# HandschuhGyro.net
KiCad netlist of a schematic drawn in EAGLE
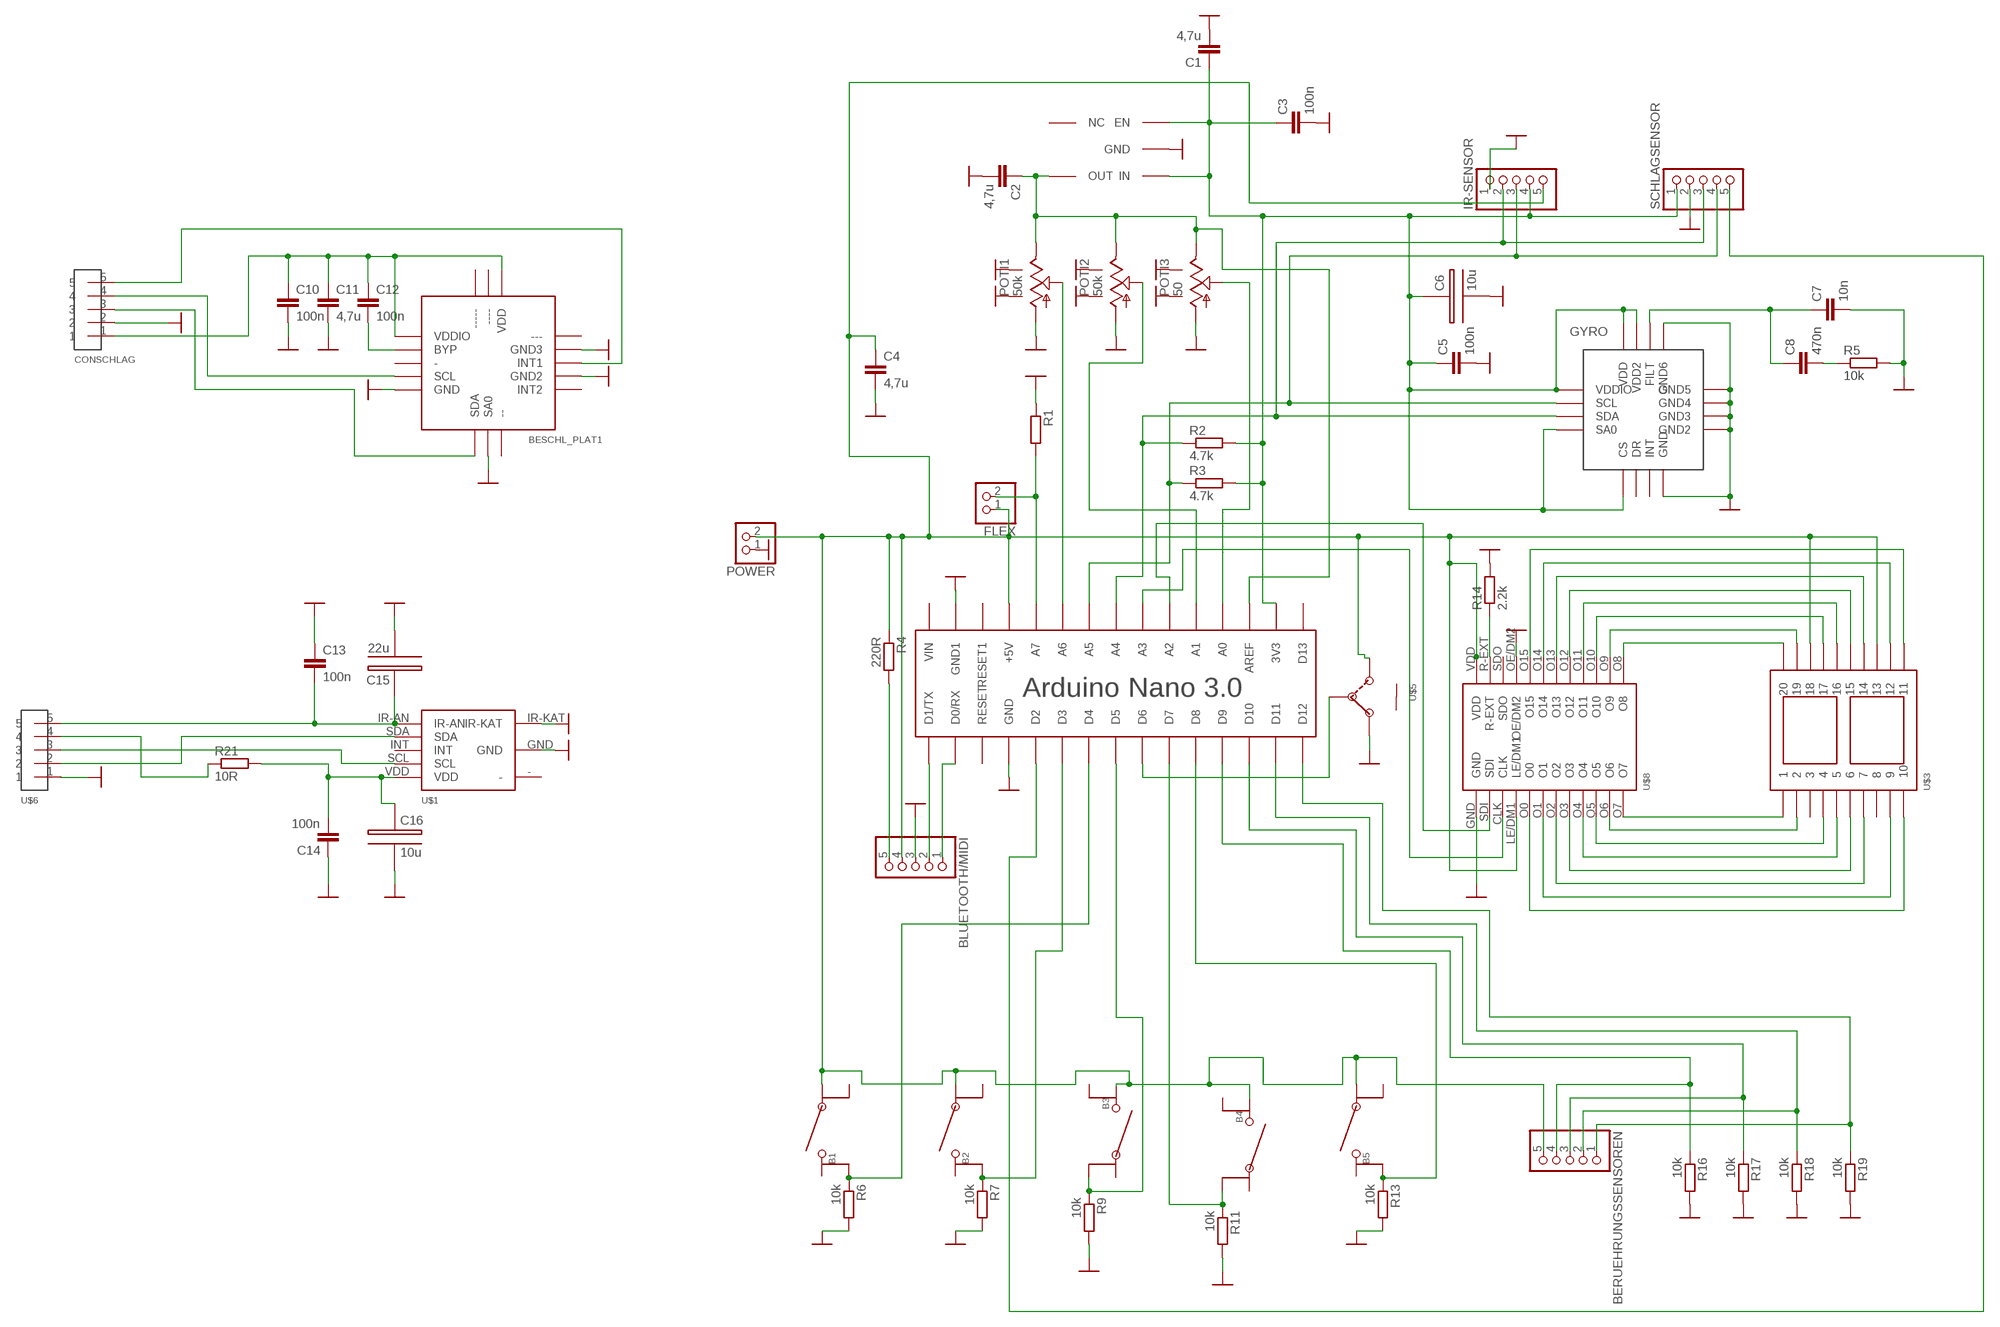
[diagram p0: schematic, sheet 1]

(export (version "E")
  (design (tool "Eeschema 10.0.6"))
  (components
    (comp (ref "B1")
      (value "BUTTON")
      (footprint "eagle-import:BUTTON")
      (libsource (lib "eagle-import") (part "BUTTON"))
    )
    (comp (ref "B2")
      (value "BUTTON")
      (footprint "eagle-import:BUTTON")
      (libsource (lib "eagle-import") (part "BUTTON"))
    )
    (comp (ref "B3")
      (value "BUTTON")
      (footprint "eagle-import:BUTTON")
      (libsource (lib "eagle-import") (part "BUTTON"))
    )
    (comp (ref "B4")
      (value "BUTTON")
      (footprint "eagle-import:BUTTON")
      (libsource (lib "eagle-import") (part "BUTTON"))
    )
    (comp (ref "B5")
      (value "BUTTON")
      (footprint "eagle-import:BUTTON")
      (libsource (lib "eagle-import") (part "BUTTON"))
    )
    (comp (ref "BERUEHRUNGSSENSOREN")
      (value "PINHD-1X5")
      (footprint "eagle-import:1X05")
      (libsource (lib "eagle-import") (part "PINHD-1X5"))
    )
    (comp (ref "BESCHL_PLAT1")
      (value "BESCHLEUNIGSUNGSSENSOR")
      (footprint "eagle-import:BESCHLEUNIGUNGSSENSOR")
      (libsource (lib "eagle-import") (part "BESCHLEUNIGSUNGSSENSOR"))
    )
    (comp (ref "BLUETOOTH/MIDI")
      (value "PINHD-1X5")
      (footprint "eagle-import:1X05")
      (libsource (lib "eagle-import") (part "PINHD-1X5"))
    )
    (comp (ref "C1")
      (value "4,7u")
      (footprint "eagle-import:C0805")
      (libsource (lib "eagle-import") (part "C-EUC0805"))
    )
    (comp (ref "C2")
      (value "4,7u")
      (footprint "eagle-import:C0805")
      (libsource (lib "eagle-import") (part "C-EUC0805"))
    )
    (comp (ref "C3")
      (value "100n")
      (footprint "eagle-import:C0805")
      (libsource (lib "eagle-import") (part "C-EUC0805"))
    )
    (comp (ref "C4")
      (value "4,7u")
      (footprint "eagle-import:C0805")
      (libsource (lib "eagle-import") (part "C-EUC0805"))
    )
    (comp (ref "C5")
      (value "100n")
      (footprint "eagle-import:C0805")
      (libsource (lib "eagle-import") (part "C-EUC0805"))
    )
    (comp (ref "C6")
      (value "10u")
      (footprint "eagle-import:22U-KONDENSATOR")
      (libsource (lib "eagle-import") (part "22U-KONDENSATOR"))
    )
    (comp (ref "C7")
      (value "10n")
      (footprint "eagle-import:C0805")
      (libsource (lib "eagle-import") (part "C-EUC0805"))
    )
    (comp (ref "C8")
      (value "470n")
      (footprint "eagle-import:C0805")
      (libsource (lib "eagle-import") (part "C-EUC0805"))
    )
    (comp (ref "C10")
      (value "100n")
      (footprint "eagle-import:C0805")
      (libsource (lib "eagle-import") (part "C-EUC0805"))
    )
    (comp (ref "C11")
      (value "4,7u")
      (footprint "eagle-import:C0805")
      (libsource (lib "eagle-import") (part "C-EUC0805"))
    )
    (comp (ref "C12")
      (value "100n")
      (footprint "eagle-import:C0805")
      (libsource (lib "eagle-import") (part "C-EUC0805"))
    )
    (comp (ref "C13")
      (value "100n")
      (footprint "eagle-import:C0805")
      (libsource (lib "eagle-import") (part "C-EUC0805"))
    )
    (comp (ref "C14")
      (value "100n")
      (footprint "eagle-import:C0805")
      (libsource (lib "eagle-import") (part "C-EUC0805"))
    )
    (comp (ref "C15")
      (value "22u")
      (footprint "eagle-import:22U-KONDENSATOR")
      (libsource (lib "eagle-import") (part "22U-KONDENSATOR"))
    )
    (comp (ref "C16")
      (value "10u")
      (footprint "eagle-import:22U-KONDENSATOR")
      (libsource (lib "eagle-import") (part "22U-KONDENSATOR"))
    )
    (comp (ref "CONSCHLAG")
      (value "BREAKBOARDCON2")
      (footprint "eagle-import:BREAKBOARDCON")
      (libsource (lib "eagle-import") (part "BREAKBOARDCON2"))
    )
    (comp (ref "FLEX")
      (value "PINHD-1X2")
      (footprint "eagle-import:1X02")
      (libsource (lib "eagle-import") (part "PINHD-1X2"))
    )
    (comp (ref "GYRO")
      (value "GYRO")
      (footprint "eagle-import:GYRO")
      (libsource (lib "eagle-import") (part "GYRO"))
    )
    (comp (ref "IR-SENSOR")
      (value "PINHD-1X5")
      (footprint "eagle-import:1X05")
      (libsource (lib "eagle-import") (part "PINHD-1X5"))
    )
    (comp (ref "POTI1")
      (value "50k")
      (footprint "eagle-import:POTI")
      (libsource (lib "eagle-import") (part "POTI"))
    )
    (comp (ref "POTI2")
      (value "50k")
      (footprint "eagle-import:POTI")
      (libsource (lib "eagle-import") (part "POTI"))
    )
    (comp (ref "POTI3")
      (value "50")
      (footprint "eagle-import:POTI")
      (libsource (lib "eagle-import") (part "POTI"))
    )
    (comp (ref "POWER")
      (value "PINHD-1X2")
      (footprint "eagle-import:1X02")
      (libsource (lib "eagle-import") (part "PINHD-1X2"))
    )
    (comp (ref "R1")
      (value "R-EU_M0805")
      (footprint "eagle-import:M0805")
      (libsource (lib "eagle-import") (part "R-EU_M0805"))
    )
    (comp (ref "R2")
      (value "4.7k")
      (footprint "eagle-import:M0805")
      (libsource (lib "eagle-import") (part "R-EU_M0805"))
    )
    (comp (ref "R3")
      (value "4.7k")
      (footprint "eagle-import:M0805")
      (libsource (lib "eagle-import") (part "R-EU_M0805"))
    )
    (comp (ref "R4")
      (value "220R")
      (footprint "eagle-import:M0805")
      (libsource (lib "eagle-import") (part "R-EU_M0805"))
    )
    (comp (ref "R5")
      (value "10k")
      (footprint "eagle-import:M0805")
      (libsource (lib "eagle-import") (part "R-EU_M0805"))
    )
    (comp (ref "R6")
      (value "10k")
      (footprint "eagle-import:M0805")
      (libsource (lib "eagle-import") (part "R-EU_M0805"))
    )
    (comp (ref "R7")
      (value "10k")
      (footprint "eagle-import:M0805")
      (libsource (lib "eagle-import") (part "R-EU_M0805"))
    )
    (comp (ref "R9")
      (value "10k")
      (footprint "eagle-import:M0805")
      (libsource (lib "eagle-import") (part "R-EU_M0805"))
    )
    (comp (ref "R11")
      (value "10k")
      (footprint "eagle-import:M0805")
      (libsource (lib "eagle-import") (part "R-EU_M0805"))
    )
    (comp (ref "R13")
      (value "10k")
      (footprint "eagle-import:M0805")
      (libsource (lib "eagle-import") (part "R-EU_M0805"))
    )
    (comp (ref "R14")
      (value "2.2k")
      (footprint "eagle-import:M0805")
      (libsource (lib "eagle-import") (part "R-EU_M0805"))
    )
    (comp (ref "R16")
      (value "10k")
      (footprint "eagle-import:M0805")
      (libsource (lib "eagle-import") (part "R-EU_M0805"))
    )
    (comp (ref "R17")
      (value "10k")
      (footprint "eagle-import:M0805")
      (libsource (lib "eagle-import") (part "R-EU_M0805"))
    )
    (comp (ref "R18")
      (value "10k")
      (footprint "eagle-import:M0805")
      (libsource (lib "eagle-import") (part "R-EU_M0805"))
    )
    (comp (ref "R19")
      (value "10k")
      (footprint "eagle-import:M0805")
      (libsource (lib "eagle-import") (part "R-EU_M0805"))
    )
    (comp (ref "R21")
      (value "10R")
      (footprint "eagle-import:M0805")
      (libsource (lib "eagle-import") (part "R-EU_M0805"))
    )
    (comp (ref "SCHLAGSENSOR")
      (value "PINHD-1X5")
      (footprint "eagle-import:1X05")
      (libsource (lib "eagle-import") (part "PINHD-1X5"))
    )
    (comp (ref "U$1")
      (value "IR-SENSOR")
      (footprint "eagle-import:IR-SENSOR")
      (libsource (lib "eagle-import") (part "IR-SENSOR"))
    )
    (comp (ref "U$2")
      (value "ARDUINONANO")
      (footprint "eagle-import:PDIP-32")
      (libsource (lib "eagle-import") (part "ARDUINONANO"))
    )
    (comp (ref "U$3")
      (value "7-SEGMENT")
      (footprint "eagle-import:7-SEGMENT")
      (libsource (lib "eagle-import") (part "7-SEGMENT"))
    )
    (comp (ref "U$4")
      (value "1,1V-SPANNUNGSREGLER")
      (footprint "eagle-import:1,1V-SPANNUNGSREGLER")
      (libsource (lib "eagle-import") (part "1,1V-SPANNUNGSREGLER"))
    )
    (comp (ref "U$5")
      (value "SCHALTER")
      (footprint "eagle-import:SCHALTER")
      (libsource (lib "eagle-import") (part "SCHALTER"))
    )
    (comp (ref "U$6")
      (value "BREAKBOARDCON2")
      (footprint "eagle-import:BREAKBOARDCON")
      (libsource (lib "eagle-import") (part "BREAKBOARDCON2"))
    )
    (comp (ref "U$8")
      (value "7-SEGMENT-TREIBER")
      (footprint "eagle-import:7-SEGMENT-TREIBER")
      (libsource (lib "eagle-import") (part "7-SEGMENT-TREIBER"))
    )
  )
  (nets
    (net (code "1") (name "Net-(B1-Pad2)") (class "Default")
      (node (ref "B1") (pin "2") (pinfunction "2_2") (pintype "bidirectional"))
      (node (ref "R6") (pin "1") (pinfunction "1_1") (pintype "passive"))
      (node (ref "U$2") (pin "D4") (pinfunction "D4_D4") (pintype "bidirectional"))
    )
    (net (code "2") (name "Net-(B1-Pad3)") (class "Default")
      (node (ref "B1") (pin "3") (pinfunction "3_3") (pintype "bidirectional"))
      (node (ref "B2") (pin "3") (pinfunction "3_3") (pintype "bidirectional"))
      (node (ref "B3") (pin "1") (pinfunction "1_1") (pintype "bidirectional"))
      (node (ref "B4") (pin "1") (pinfunction "1_1") (pintype "bidirectional"))
      (node (ref "B5") (pin "3") (pinfunction "3_3") (pintype "bidirectional"))
      (node (ref "BERUEHRUNGSSENSOREN") (pin "5") (pinfunction "5_5") (pintype "passive"))
      (node (ref "BLUETOOTH/MIDI") (pin "4") (pinfunction "4_4") (pintype "passive"))
      (node (ref "C4") (pin "1") (pinfunction "1_1") (pintype "passive"))
      (node (ref "FLEX") (pin "1") (pinfunction "1_1") (pintype "passive"))
      (node (ref "IR-SENSOR") (pin "5") (pinfunction "5_5") (pintype "passive"))
      (node (ref "POWER") (pin "2") (pinfunction "2_2") (pintype "passive"))
      (node (ref "R4") (pin "1") (pinfunction "1_1") (pintype "passive"))
      (node (ref "U$2") (pin "+5V") (pinfunction "+5V_+5V") (pintype "bidirectional"))
      (node (ref "U$3") (pin "13") (pinfunction "13_13") (pintype "bidirectional"))
      (node (ref "U$3") (pin "18") (pinfunction "18_18") (pintype "bidirectional"))
      (node (ref "U$5") (pin "3") (pinfunction "3_3") (pintype "bidirectional"))
      (node (ref "U$8") (pin "LE/DM1") (pinfunction "LE/DM1_LE/DM1") (pintype "bidirectional"))
      (node (ref "U$8") (pin "VDD") (pinfunction "VDD_VDD") (pintype "bidirectional"))
    )
    (net (code "3") (name "Net-(B2-Pad2)") (class "Default")
      (node (ref "B2") (pin "2") (pinfunction "2_2") (pintype "bidirectional"))
      (node (ref "R7") (pin "1") (pinfunction "1_1") (pintype "passive"))
      (node (ref "U$2") (pin "D3") (pinfunction "D3_D3") (pintype "bidirectional"))
    )
    (net (code "4") (name "Net-(B3-Pad4)") (class "Default")
      (node (ref "B3") (pin "4") (pinfunction "4_4") (pintype "bidirectional"))
      (node (ref "R9") (pin "1") (pinfunction "1_1") (pintype "passive"))
      (node (ref "U$2") (pin "D5") (pinfunction "D5_D5") (pintype "bidirectional"))
    )
    (net (code "5") (name "Net-(B4-Pad4)") (class "Default")
      (node (ref "B4") (pin "4") (pinfunction "4_4") (pintype "bidirectional"))
      (node (ref "R11") (pin "1") (pinfunction "1_1") (pintype "passive"))
      (node (ref "U$2") (pin "D7") (pinfunction "D7_D7") (pintype "bidirectional"))
    )
    (net (code "6") (name "Net-(B5-Pad2)") (class "Default")
      (node (ref "B5") (pin "2") (pinfunction "2_2") (pintype "bidirectional"))
      (node (ref "R13") (pin "1") (pinfunction "1_1") (pintype "passive"))
      (node (ref "U$2") (pin "D8") (pinfunction "D8_D8") (pintype "bidirectional"))
    )
    (net (code "7") (name "Net-(BERUEHRUNGSSENSOREN-Pad1)") (class "Default")
      (node (ref "BERUEHRUNGSSENSOREN") (pin "1") (pinfunction "1_1") (pintype "passive"))
      (node (ref "R19") (pin "1") (pinfunction "1_1") (pintype "passive"))
      (node (ref "U$2") (pin "D12") (pinfunction "D12_D12") (pintype "bidirectional"))
    )
    (net (code "8") (name "Net-(BERUEHRUNGSSENSOREN-Pad2)") (class "Default")
      (node (ref "BERUEHRUNGSSENSOREN") (pin "2") (pinfunction "2_2") (pintype "passive"))
      (node (ref "R18") (pin "1") (pinfunction "1_1") (pintype "passive"))
      (node (ref "U$2") (pin "D11") (pinfunction "D11_D11") (pintype "bidirectional"))
    )
    (net (code "9") (name "Net-(BERUEHRUNGSSENSOREN-Pad3)") (class "Default")
      (node (ref "BERUEHRUNGSSENSOREN") (pin "3") (pinfunction "3_3") (pintype "passive"))
      (node (ref "R17") (pin "1") (pinfunction "1_1") (pintype "passive"))
      (node (ref "U$2") (pin "D10") (pinfunction "D10_D10") (pintype "bidirectional"))
    )
    (net (code "10") (name "Net-(BERUEHRUNGSSENSOREN-Pad4)") (class "Default")
      (node (ref "BERUEHRUNGSSENSOREN") (pin "4") (pinfunction "4_4") (pintype "passive"))
      (node (ref "R16") (pin "1") (pinfunction "1_1") (pintype "passive"))
      (node (ref "U$2") (pin "D9") (pinfunction "D9_D9") (pintype "bidirectional"))
    )
    (net (code "11") (name "Net-(BESCHL_PLAT1-PadBYP)") (class "Default")
      (node (ref "BESCHL_PLAT1") (pin "BYP") (pinfunction "BYP_BYP") (pintype "bidirectional"))
      (node (ref "C12") (pin "2") (pinfunction "2_2") (pintype "passive"))
    )
    (net (code "12") (name "Net-(BESCHL_PLAT1-PadINT1)") (class "Default")
      (node (ref "BESCHL_PLAT1") (pin "INT1") (pinfunction "INT1_INT1") (pintype "bidirectional"))
      (node (ref "CONSCHLAG") (pin "5") (pinfunction "5_5") (pintype "bidirectional"))
    )
    (net (code "13") (name "Net-(BESCHL_PLAT1-PadSCL)") (class "Default")
      (node (ref "BESCHL_PLAT1") (pin "SCL") (pinfunction "SCL_SCL") (pintype "bidirectional"))
      (node (ref "CONSCHLAG") (pin "4") (pinfunction "4_4") (pintype "bidirectional"))
    )
    (net (code "14") (name "Net-(BESCHL_PLAT1-PadSDA)") (class "Default")
      (node (ref "BESCHL_PLAT1") (pin "SDA") (pinfunction "SDA_SDA") (pintype "bidirectional"))
      (node (ref "CONSCHLAG") (pin "3") (pinfunction "3_3") (pintype "bidirectional"))
    )
    (net (code "15") (name "Net-(BESCHL_PLAT1-PadVDD)") (class "Default")
      (node (ref "BESCHL_PLAT1") (pin "VDD") (pinfunction "VDD_VDD") (pintype "bidirectional"))
      (node (ref "BESCHL_PLAT1") (pin "VDDIO") (pinfunction "VDDIO_VDDIO") (pintype "bidirectional"))
      (node (ref "C10") (pin "1") (pinfunction "1_1") (pintype "passive"))
      (node (ref "C11") (pin "1") (pinfunction "1_1") (pintype "passive"))
      (node (ref "C12") (pin "1") (pinfunction "1_1") (pintype "passive"))
      (node (ref "CONSCHLAG") (pin "1") (pinfunction "1_1") (pintype "bidirectional"))
    )
    (net (code "16") (name "Net-(BLUETOOTH/MIDI-Pad1)") (class "Default")
      (node (ref "BLUETOOTH/MIDI") (pin "1") (pinfunction "1_1") (pintype "passive"))
      (node (ref "U$2") (pin "D0/RX") (pinfunction "D0/RX_D0/RX") (pintype "bidirectional"))
    )
    (net (code "17") (name "Net-(BLUETOOTH/MIDI-Pad2)") (class "Default")
      (node (ref "BLUETOOTH/MIDI") (pin "2") (pinfunction "2_2") (pintype "passive"))
      (node (ref "U$2") (pin "D1/TX") (pinfunction "D1/TX_D1/TX") (pintype "bidirectional"))
    )
    (net (code "18") (name "Net-(BLUETOOTH/MIDI-Pad5)") (class "Default")
      (node (ref "BLUETOOTH/MIDI") (pin "5") (pinfunction "5_5") (pintype "passive"))
      (node (ref "R4") (pin "2") (pinfunction "2_2") (pintype "passive"))
    )
    (net (code "19") (name "Net-(C1-Pad1)") (class "Default")
      (node (ref "C1") (pin "1") (pinfunction "1_1") (pintype "passive"))
      (node (ref "C3") (pin "1") (pinfunction "1_1") (pintype "passive"))
      (node (ref "C5") (pin "1") (pinfunction "1_1") (pintype "passive"))
      (node (ref "C6") (pin "+") (pinfunction "+_+") (pintype "bidirectional"))
      (node (ref "GYRO") (pin "CS") (pinfunction "CS_CS") (pintype "bidirectional"))
      (node (ref "GYRO") (pin "SA0") (pinfunction "SA0_SA0") (pintype "bidirectional"))
      (node (ref "GYRO") (pin "VDD") (pinfunction "VDD_VDD") (pintype "bidirectional"))
      (node (ref "GYRO") (pin "VDD2") (pinfunction "VDD2_VDD2") (pintype "bidirectional"))
      (node (ref "GYRO") (pin "VDDIO") (pinfunction "VDDIO_VDDIO") (pintype "bidirectional"))
      (node (ref "IR-SENSOR") (pin "4") (pinfunction "4_4") (pintype "passive"))
      (node (ref "R2") (pin "2") (pinfunction "2_2") (pintype "passive"))
      (node (ref "R3") (pin "2") (pinfunction "2_2") (pintype "passive"))
      (node (ref "SCHLAGSENSOR") (pin "1") (pinfunction "1_1") (pintype "passive"))
      (node (ref "U$2") (pin "3V3") (pinfunction "3V3_3V3") (pintype "bidirectional"))
      (node (ref "U$4") (pin "EN") (pinfunction "EN_EN") (pintype "bidirectional"))
      (node (ref "U$4") (pin "IN") (pinfunction "IN_IN") (pintype "bidirectional"))
    )
    (net (code "20") (name "Net-(C2-Pad1)") (class "Default")
      (node (ref "C2") (pin "1") (pinfunction "1_1") (pintype "passive"))
      (node (ref "POTI1") (pin "VCC") (pinfunction "VCC_VCC") (pintype "passive"))
      (node (ref "POTI2") (pin "VCC") (pinfunction "VCC_VCC") (pintype "passive"))
      (node (ref "POTI3") (pin "VCC") (pinfunction "VCC_VCC") (pintype "passive"))
      (node (ref "U$2") (pin "AREF") (pinfunction "AREF_AREF") (pintype "bidirectional"))
      (node (ref "U$4") (pin "OUT") (pinfunction "OUT_OUT") (pintype "bidirectional"))
    )
    (net (code "21") (name "Net-(C7-Pad1)") (class "Default")
      (node (ref "C7") (pin "1") (pinfunction "1_1") (pintype "passive"))
      (node (ref "C8") (pin "1") (pinfunction "1_1") (pintype "passive"))
      (node (ref "GYRO") (pin "FILT") (pinfunction "FILT_FILT") (pintype "bidirectional"))
    )
    (net (code "22") (name "Net-(C8-Pad2)") (class "Default")
      (node (ref "C8") (pin "2") (pinfunction "2_2") (pintype "passive"))
      (node (ref "R5") (pin "1") (pinfunction "1_1") (pintype "passive"))
    )
    (net (code "23") (name "Net-(C13-Pad2)") (class "Default")
      (node (ref "C13") (pin "2") (pinfunction "2_2") (pintype "passive"))
      (node (ref "C15") (pin "+") (pinfunction "+_+") (pintype "bidirectional"))
      (node (ref "U$1") (pin "IR-AN") (pinfunction "IR-AN_IR-AN") (pintype "bidirectional"))
      (node (ref "U$6") (pin "5") (pinfunction "5_5") (pintype "bidirectional"))
    )
    (net (code "24") (name "Net-(C14-Pad2)") (class "Default")
      (node (ref "C14") (pin "2") (pinfunction "2_2") (pintype "passive"))
      (node (ref "C16") (pin "+") (pinfunction "+_+") (pintype "bidirectional"))
      (node (ref "R21") (pin "2") (pinfunction "2_2") (pintype "passive"))
      (node (ref "U$1") (pin "VDD") (pinfunction "VDD_VDD") (pintype "bidirectional"))
    )
    (net (code "25") (name "Net-(R14-Pad1)") (class "Default")
      (node (ref "R14") (pin "1") (pinfunction "1_1") (pintype "passive"))
      (node (ref "U$8") (pin "R-EXT") (pinfunction "R-EXT_R-EXT") (pintype "bidirectional"))
    )
    (net (code "26") (name "Net-(R21-Pad1)") (class "Default")
      (node (ref "R21") (pin "1") (pinfunction "1_1") (pintype "passive"))
      (node (ref "U$6") (pin "4") (pinfunction "4_4") (pintype "bidirectional"))
    )
    (net (code "27") (name "Net-(SCHLAGSENSOR-Pad5)") (class "Default")
      (node (ref "SCHLAGSENSOR") (pin "5") (pinfunction "5_5") (pintype "passive"))
      (node (ref "U$2") (pin "D2") (pinfunction "D2_D2") (pintype "bidirectional"))
    )
    (net (code "28") (name "Net-(U$1-PadSCL)") (class "Default")
      (node (ref "U$1") (pin "SCL") (pinfunction "SCL_SCL") (pintype "bidirectional"))
      (node (ref "U$6") (pin "3") (pinfunction "3_3") (pintype "bidirectional"))
    )
    (net (code "29") (name "Net-(U$1-PadSDA)") (class "Default")
      (node (ref "U$1") (pin "SDA") (pinfunction "SDA_SDA") (pintype "bidirectional"))
      (node (ref "U$6") (pin "2") (pinfunction "2_2") (pintype "bidirectional"))
    )
    (net (code "30") (name "Net-(U$2-A0)") (class "Default")
      (node (ref "POTI3") (pin "VALUE") (pinfunction "VALUE_VALUE") (pintype "passive"))
      (node (ref "U$2") (pin "A7") (pinfunction "A0_A7") (pintype "bidirectional"))
    )
    (net (code "31") (name "Net-(U$2-A1)") (class "Default")
      (node (ref "POTI2") (pin "VALUE") (pinfunction "VALUE_VALUE") (pintype "passive"))
      (node (ref "U$2") (pin "A6") (pinfunction "A1_A6") (pintype "bidirectional"))
    )
    (net (code "32") (name "Net-(U$2-A2)") (class "Default")
      (node (ref "U$2") (pin "A5") (pinfunction "A2_A5") (pintype "bidirectional"))
      (node (ref "U$8") (pin "SDI") (pinfunction "SDI_SDI") (pintype "bidirectional"))
    )
    (net (code "33") (name "Net-(U$2-A3)") (class "Default")
      (node (ref "U$2") (pin "A4") (pinfunction "A3_A4") (pintype "bidirectional"))
      (node (ref "U$8") (pin "CLK") (pinfunction "CLK_CLK") (pintype "bidirectional"))
    )
    (net (code "34") (name "Net-(U$2-A4)") (class "Default")
      (node (ref "GYRO") (pin "SDA") (pinfunction "SDA_SDA") (pintype "bidirectional"))
      (node (ref "IR-SENSOR") (pin "2") (pinfunction "2_2") (pintype "passive"))
      (node (ref "R2") (pin "1") (pinfunction "1_1") (pintype "passive"))
      (node (ref "SCHLAGSENSOR") (pin "3") (pinfunction "3_3") (pintype "passive"))
      (node (ref "U$2") (pin "A3") (pinfunction "A4_A3") (pintype "bidirectional"))
    )
    (net (code "35") (name "Net-(U$2-A5)") (class "Default")
      (node (ref "GYRO") (pin "SCL") (pinfunction "SCL_SCL") (pintype "bidirectional"))
      (node (ref "IR-SENSOR") (pin "3") (pinfunction "3_3") (pintype "passive"))
      (node (ref "R3") (pin "1") (pinfunction "1_1") (pintype "passive"))
      (node (ref "SCHLAGSENSOR") (pin "4") (pinfunction "4_4") (pintype "passive"))
      (node (ref "U$2") (pin "A2") (pinfunction "A5_A2") (pintype "bidirectional"))
    )
    (net (code "36") (name "Net-(U$2-A6)") (class "Default")
      (node (ref "POTI1") (pin "VALUE") (pinfunction "VALUE_VALUE") (pintype "passive"))
      (node (ref "U$2") (pin "A1") (pinfunction "A6_A1") (pintype "bidirectional"))
    )
    (net (code "37") (name "Net-(U$2-A7)") (class "Default")
      (node (ref "FLEX") (pin "2") (pinfunction "2_2") (pintype "passive"))
      (node (ref "R1") (pin "2") (pinfunction "2_2") (pintype "passive"))
      (node (ref "U$2") (pin "A0") (pinfunction "A7_A0") (pintype "bidirectional"))
    )
    (net (code "38") (name "Net-(U$2-PadD6)") (class "Default")
      (node (ref "U$2") (pin "D6") (pinfunction "D6_D6") (pintype "bidirectional"))
      (node (ref "U$5") (pin "2") (pinfunction "2_2") (pintype "bidirectional"))
    )
    (net (code "39") (name "Net-(U$3-Pad1)") (class "Default")
      (node (ref "U$3") (pin "1") (pinfunction "1_1") (pintype "bidirectional"))
      (node (ref "U$8") (pin "O7") (pinfunction "O7_O7") (pintype "bidirectional"))
    )
    (net (code "40") (name "Net-(U$3-Pad2)") (class "Default")
      (node (ref "U$3") (pin "2") (pinfunction "2_2") (pintype "bidirectional"))
      (node (ref "U$8") (pin "O6") (pinfunction "O6_O6") (pintype "bidirectional"))
    )
    (net (code "41") (name "Net-(U$3-Pad4)") (class "Default")
      (node (ref "U$3") (pin "4") (pinfunction "4_4") (pintype "bidirectional"))
      (node (ref "U$8") (pin "O5") (pinfunction "O5_O5") (pintype "bidirectional"))
    )
    (net (code "42") (name "Net-(U$3-Pad5)") (class "Default")
      (node (ref "U$3") (pin "5") (pinfunction "5_5") (pintype "bidirectional"))
      (node (ref "U$8") (pin "O4") (pinfunction "O4_O4") (pintype "bidirectional"))
    )
    (net (code "43") (name "Net-(U$3-Pad6)") (class "Default")
      (node (ref "U$3") (pin "6") (pinfunction "6_6") (pintype "bidirectional"))
      (node (ref "U$8") (pin "O3") (pinfunction "O3_O3") (pintype "bidirectional"))
    )
    (net (code "44") (name "Net-(U$3-Pad7)") (class "Default")
      (node (ref "U$3") (pin "7") (pinfunction "7_7") (pintype "bidirectional"))
      (node (ref "U$8") (pin "O2") (pinfunction "O2_O2") (pintype "bidirectional"))
    )
    (net (code "45") (name "Net-(U$3-Pad9)") (class "Default")
      (node (ref "U$3") (pin "9") (pinfunction "9_9") (pintype "bidirectional"))
      (node (ref "U$8") (pin "O1") (pinfunction "O1_O1") (pintype "bidirectional"))
    )
    (net (code "46") (name "Net-(U$3-Pad10)") (class "Default")
      (node (ref "U$3") (pin "10") (pinfunction "10_10") (pintype "bidirectional"))
      (node (ref "U$8") (pin "O0") (pinfunction "O0_O0") (pintype "bidirectional"))
    )
    (net (code "47") (name "Net-(U$3-Pad11)") (class "Default")
      (node (ref "U$3") (pin "11") (pinfunction "11_11") (pintype "bidirectional"))
      (node (ref "U$8") (pin "O15") (pinfunction "O15_O15") (pintype "bidirectional"))
    )
    (net (code "48") (name "Net-(U$3-Pad12)") (class "Default")
      (node (ref "U$3") (pin "12") (pinfunction "12_12") (pintype "bidirectional"))
      (node (ref "U$8") (pin "O14") (pinfunction "O14_O14") (pintype "bidirectional"))
    )
    (net (code "49") (name "Net-(U$3-Pad14)") (class "Default")
      (node (ref "U$3") (pin "14") (pinfunction "14_14") (pintype "bidirectional"))
      (node (ref "U$8") (pin "O13") (pinfunction "O13_O13") (pintype "bidirectional"))
    )
    (net (code "50") (name "Net-(U$3-Pad15)") (class "Default")
      (node (ref "U$3") (pin "15") (pinfunction "15_15") (pintype "bidirectional"))
      (node (ref "U$8") (pin "O12") (pinfunction "O12_O12") (pintype "bidirectional"))
    )
    (net (code "51") (name "Net-(U$3-Pad16)") (class "Default")
      (node (ref "U$3") (pin "16") (pinfunction "16_16") (pintype "bidirectional"))
      (node (ref "U$8") (pin "O11") (pinfunction "O11_O11") (pintype "bidirectional"))
    )
    (net (code "52") (name "Net-(U$3-Pad17)") (class "Default")
      (node (ref "U$3") (pin "17") (pinfunction "17_17") (pintype "bidirectional"))
      (node (ref "U$8") (pin "O10") (pinfunction "O10_O10") (pintype "bidirectional"))
    )
    (net (code "53") (name "Net-(U$3-Pad19)") (class "Default")
      (node (ref "U$3") (pin "19") (pinfunction "19_19") (pintype "bidirectional"))
      (node (ref "U$8") (pin "O9") (pinfunction "O9_O9") (pintype "bidirectional"))
    )
    (net (code "54") (name "Net-(U$3-Pad20)") (class "Default")
      (node (ref "U$3") (pin "20") (pinfunction "20_20") (pintype "bidirectional"))
      (node (ref "U$8") (pin "O8") (pinfunction "O8_O8") (pintype "bidirectional"))
    )
    (net (code "55") (name "POWER_SUPPLY1_GND") (class "Default")
      (node (ref "BESCHL_PLAT1") (pin "GND") (pinfunction "GND_GND") (pintype "bidirectional"))
      (node (ref "BESCHL_PLAT1") (pin "GND2") (pinfunction "GND2_GND2") (pintype "bidirectional"))
      (node (ref "BESCHL_PLAT1") (pin "GND3") (pinfunction "GND3_GND3") (pintype "bidirectional"))
      (node (ref "BESCHL_PLAT1") (pin "SA0") (pinfunction "SA0_SA0") (pintype "bidirectional"))
      (node (ref "BLUETOOTH/MIDI") (pin "3") (pinfunction "3_3") (pintype "passive"))
      (node (ref "C1") (pin "2") (pinfunction "2_2") (pintype "passive"))
      (node (ref "C10") (pin "2") (pinfunction "2_2") (pintype "passive"))
      (node (ref "C11") (pin "2") (pinfunction "2_2") (pintype "passive"))
      (node (ref "C13") (pin "1") (pinfunction "1_1") (pintype "passive"))
      (node (ref "C14") (pin "1") (pinfunction "1_1") (pintype "passive"))
      (node (ref "C15") (pin "-") (pinfunction "-_-") (pintype "bidirectional"))
      (node (ref "C16") (pin "-") (pinfunction "-_-") (pintype "bidirectional"))
      (node (ref "C2") (pin "2") (pinfunction "2_2") (pintype "passive"))
      (node (ref "C3") (pin "2") (pinfunction "2_2") (pintype "passive"))
      (node (ref "C4") (pin "2") (pinfunction "2_2") (pintype "passive"))
      (node (ref "C5") (pin "2") (pinfunction "2_2") (pintype "passive"))
      (node (ref "C6") (pin "-") (pinfunction "-_-") (pintype "bidirectional"))
      (node (ref "C7") (pin "2") (pinfunction "2_2") (pintype "passive"))
      (node (ref "CONSCHLAG") (pin "2") (pinfunction "2_2") (pintype "bidirectional"))
      (node (ref "GYRO") (pin "GND") (pinfunction "GND_GND") (pintype "bidirectional"))
      (node (ref "GYRO") (pin "GND2") (pinfunction "GND2_GND2") (pintype "bidirectional"))
      (node (ref "GYRO") (pin "GND3") (pinfunction "GND3_GND3") (pintype "bidirectional"))
      (node (ref "GYRO") (pin "GND4") (pinfunction "GND4_GND4") (pintype "bidirectional"))
      (node (ref "GYRO") (pin "GND5") (pinfunction "GND5_GND5") (pintype "bidirectional"))
      (node (ref "GYRO") (pin "GND6") (pinfunction "GND6_GND6") (pintype "bidirectional"))
      (node (ref "IR-SENSOR") (pin "1") (pinfunction "1_1") (pintype "passive"))
      (node (ref "POTI1") (pin "FIX1") (pinfunction "FUSS1_FIX1") (pintype "passive"))
      (node (ref "POTI1") (pin "FIX2") (pinfunction "FUSS2_FIX2") (pintype "passive"))
      (node (ref "POTI1") (pin "GND") (pinfunction "GND_GND") (pintype "passive"))
      (node (ref "POTI2") (pin "FIX1") (pinfunction "FUSS1_FIX1") (pintype "passive"))
      (node (ref "POTI2") (pin "FIX2") (pinfunction "FUSS2_FIX2") (pintype "passive"))
      (node (ref "POTI2") (pin "GND") (pinfunction "GND_GND") (pintype "passive"))
      (node (ref "POTI3") (pin "FIX1") (pinfunction "FUSS1_FIX1") (pintype "passive"))
      (node (ref "POTI3") (pin "FIX2") (pinfunction "FUSS2_FIX2") (pintype "passive"))
      (node (ref "POTI3") (pin "GND") (pinfunction "GND_GND") (pintype "passive"))
      (node (ref "POWER") (pin "1") (pinfunction "1_1") (pintype "passive"))
      (node (ref "R1") (pin "1") (pinfunction "1_1") (pintype "passive"))
      (node (ref "R11") (pin "2") (pinfunction "2_2") (pintype "passive"))
      (node (ref "R13") (pin "2") (pinfunction "2_2") (pintype "passive"))
      (node (ref "R14") (pin "2") (pinfunction "2_2") (pintype "passive"))
      (node (ref "R16") (pin "2") (pinfunction "2_2") (pintype "passive"))
      (node (ref "R17") (pin "2") (pinfunction "2_2") (pintype "passive"))
      (node (ref "R18") (pin "2") (pinfunction "2_2") (pintype "passive"))
      (node (ref "R19") (pin "2") (pinfunction "2_2") (pintype "passive"))
      (node (ref "R5") (pin "2") (pinfunction "2_2") (pintype "passive"))
      (node (ref "R6") (pin "2") (pinfunction "2_2") (pintype "passive"))
      (node (ref "R7") (pin "2") (pinfunction "2_2") (pintype "passive"))
      (node (ref "R9") (pin "2") (pinfunction "2_2") (pintype "passive"))
      (node (ref "SCHLAGSENSOR") (pin "2") (pinfunction "2_2") (pintype "passive"))
      (node (ref "U$1") (pin "GND") (pinfunction "GND_GND") (pintype "bidirectional"))
      (node (ref "U$1") (pin "IR-KAT") (pinfunction "IR-KAT_IR-KAT") (pintype "bidirectional"))
      (node (ref "U$2") (pin "GND") (pinfunction "GND_GND") (pintype "bidirectional"))
      (node (ref "U$2") (pin "GND1") (pinfunction "GND1_GND1") (pintype "bidirectional"))
      (node (ref "U$4") (pin "GND") (pinfunction "GND_GND") (pintype "bidirectional"))
      (node (ref "U$5") (pin "1") (pinfunction "1_1") (pintype "bidirectional"))
      (node (ref "U$6") (pin "1") (pinfunction "1_1") (pintype "bidirectional"))
      (node (ref "U$8") (pin "GND") (pinfunction "GND_GND") (pintype "bidirectional"))
      (node (ref "U$8") (pin "OE/DM2") (pinfunction "OE/DM2_OE/DM2") (pintype "bidirectional"))
    )
    (net (code "56") (name "unconnected-(B1-Pad1)") (class "Default")
      (node (ref "B1") (pin "1") (pinfunction "1_1") (pintype "bidirectional"))
    )
    (net (code "57") (name "unconnected-(B1-Pad4)") (class "Default")
      (node (ref "B1") (pin "4") (pinfunction "4_4") (pintype "bidirectional"))
    )
    (net (code "58") (name "unconnected-(B2-Pad1)") (class "Default")
      (node (ref "B2") (pin "1") (pinfunction "1_1") (pintype "bidirectional"))
    )
    (net (code "59") (name "unconnected-(B2-Pad4)") (class "Default")
      (node (ref "B2") (pin "4") (pinfunction "4_4") (pintype "bidirectional"))
    )
    (net (code "60") (name "unconnected-(B3-Pad2)") (class "Default")
      (node (ref "B3") (pin "2") (pinfunction "2_2") (pintype "bidirectional"))
    )
    (net (code "61") (name "unconnected-(B3-Pad3)") (class "Default")
      (node (ref "B3") (pin "3") (pinfunction "3_3") (pintype "bidirectional"))
    )
    (net (code "62") (name "unconnected-(B4-Pad2)") (class "Default")
      (node (ref "B4") (pin "2") (pinfunction "2_2") (pintype "bidirectional"))
    )
    (net (code "63") (name "unconnected-(B4-Pad3)") (class "Default")
      (node (ref "B4") (pin "3") (pinfunction "3_3") (pintype "bidirectional"))
    )
    (net (code "64") (name "unconnected-(B5-Pad1)") (class "Default")
      (node (ref "B5") (pin "1") (pinfunction "1_1") (pintype "bidirectional"))
    )
    (net (code "65") (name "unconnected-(B5-Pad4)") (class "Default")
      (node (ref "B5") (pin "4") (pinfunction "4_4") (pintype "bidirectional"))
    )
    (net (code "66") (name "unconnected-(BESCHL_PLAT1-Pad-)") (class "Default")
      (node (ref "BESCHL_PLAT1") (pin "-") (pinfunction "-_-") (pintype "bidirectional"))
    )
    (net (code "67") (name "unconnected-(BESCHL_PLAT1-Pad--)") (class "Default")
      (node (ref "BESCHL_PLAT1") (pin "--") (pinfunction "--_--") (pintype "bidirectional"))
    )
    (net (code "68") (name "unconnected-(BESCHL_PLAT1-Pad---)") (class "Default")
      (node (ref "BESCHL_PLAT1") (pin "---") (pinfunction "---_---") (pintype "bidirectional"))
    )
    (net (code "69") (name "unconnected-(BESCHL_PLAT1-Pad----)") (class "Default")
      (node (ref "BESCHL_PLAT1") (pin "----") (pinfunction "----_----") (pintype "bidirectional"))
    )
    (net (code "70") (name "unconnected-(BESCHL_PLAT1-Pad-----)") (class "Default")
      (node (ref "BESCHL_PLAT1") (pin "-----") (pinfunction "-----_-----") (pintype "bidirectional"))
    )
    (net (code "71") (name "unconnected-(BESCHL_PLAT1-PadINT2)") (class "Default")
      (node (ref "BESCHL_PLAT1") (pin "INT2") (pinfunction "INT2_INT2") (pintype "bidirectional"))
    )
    (net (code "72") (name "unconnected-(GYRO-PadDR)") (class "Default")
      (node (ref "GYRO") (pin "DR") (pinfunction "DR_DR") (pintype "bidirectional"))
    )
    (net (code "73") (name "unconnected-(GYRO-PadINT)") (class "Default")
      (node (ref "GYRO") (pin "INT") (pinfunction "INT_INT") (pintype "bidirectional"))
    )
    (net (code "74") (name "unconnected-(U$1-Pad-)") (class "Default")
      (node (ref "U$1") (pin "-") (pinfunction "-_-") (pintype "bidirectional"))
    )
    (net (code "75") (name "unconnected-(U$1-PadINT)") (class "Default")
      (node (ref "U$1") (pin "INT") (pinfunction "INT_INT") (pintype "bidirectional"))
    )
    (net (code "76") (name "unconnected-(U$2-PadD13)") (class "Default")
      (node (ref "U$2") (pin "D13") (pinfunction "D13_D13") (pintype "bidirectional"))
    )
    (net (code "77") (name "unconnected-(U$2-PadRESET)") (class "Default")
      (node (ref "U$2") (pin "RESET") (pinfunction "RESET_RESET") (pintype "bidirectional"))
    )
    (net (code "78") (name "unconnected-(U$2-PadRESET1)") (class "Default")
      (node (ref "U$2") (pin "RESET1") (pinfunction "RESET1_RESET1") (pintype "bidirectional"))
    )
    (net (code "79") (name "unconnected-(U$2-PadVIN)") (class "Default")
      (node (ref "U$2") (pin "VIN") (pinfunction "VIN_VIN") (pintype "bidirectional"))
    )
    (net (code "80") (name "unconnected-(U$3-Pad3)") (class "Default")
      (node (ref "U$3") (pin "3") (pinfunction "3_3") (pintype "bidirectional"))
    )
    (net (code "81") (name "unconnected-(U$3-Pad8)") (class "Default")
      (node (ref "U$3") (pin "8") (pinfunction "8_8") (pintype "bidirectional"))
    )
    (net (code "82") (name "unconnected-(U$4-PadNC)") (class "Default")
      (node (ref "U$4") (pin "NC") (pinfunction "NC_NC") (pintype "bidirectional"))
    )
    (net (code "83") (name "unconnected-(U$5-Pad4)") (class "Default")
      (node (ref "U$5") (pin "4") (pinfunction "4_4") (pintype "bidirectional"))
    )
    (net (code "84") (name "unconnected-(U$5-Pad5)") (class "Default")
      (node (ref "U$5") (pin "5") (pinfunction "5_5") (pintype "bidirectional"))
    )
    (net (code "85") (name "unconnected-(U$8-PadSDO)") (class "Default")
      (node (ref "U$8") (pin "SDO") (pinfunction "SDO_SDO") (pintype "bidirectional"))
    )
  )
)
